# lab1_arhipov_usb_i2c.net
KiCad netlist of a schematic drawn in Altium Designer
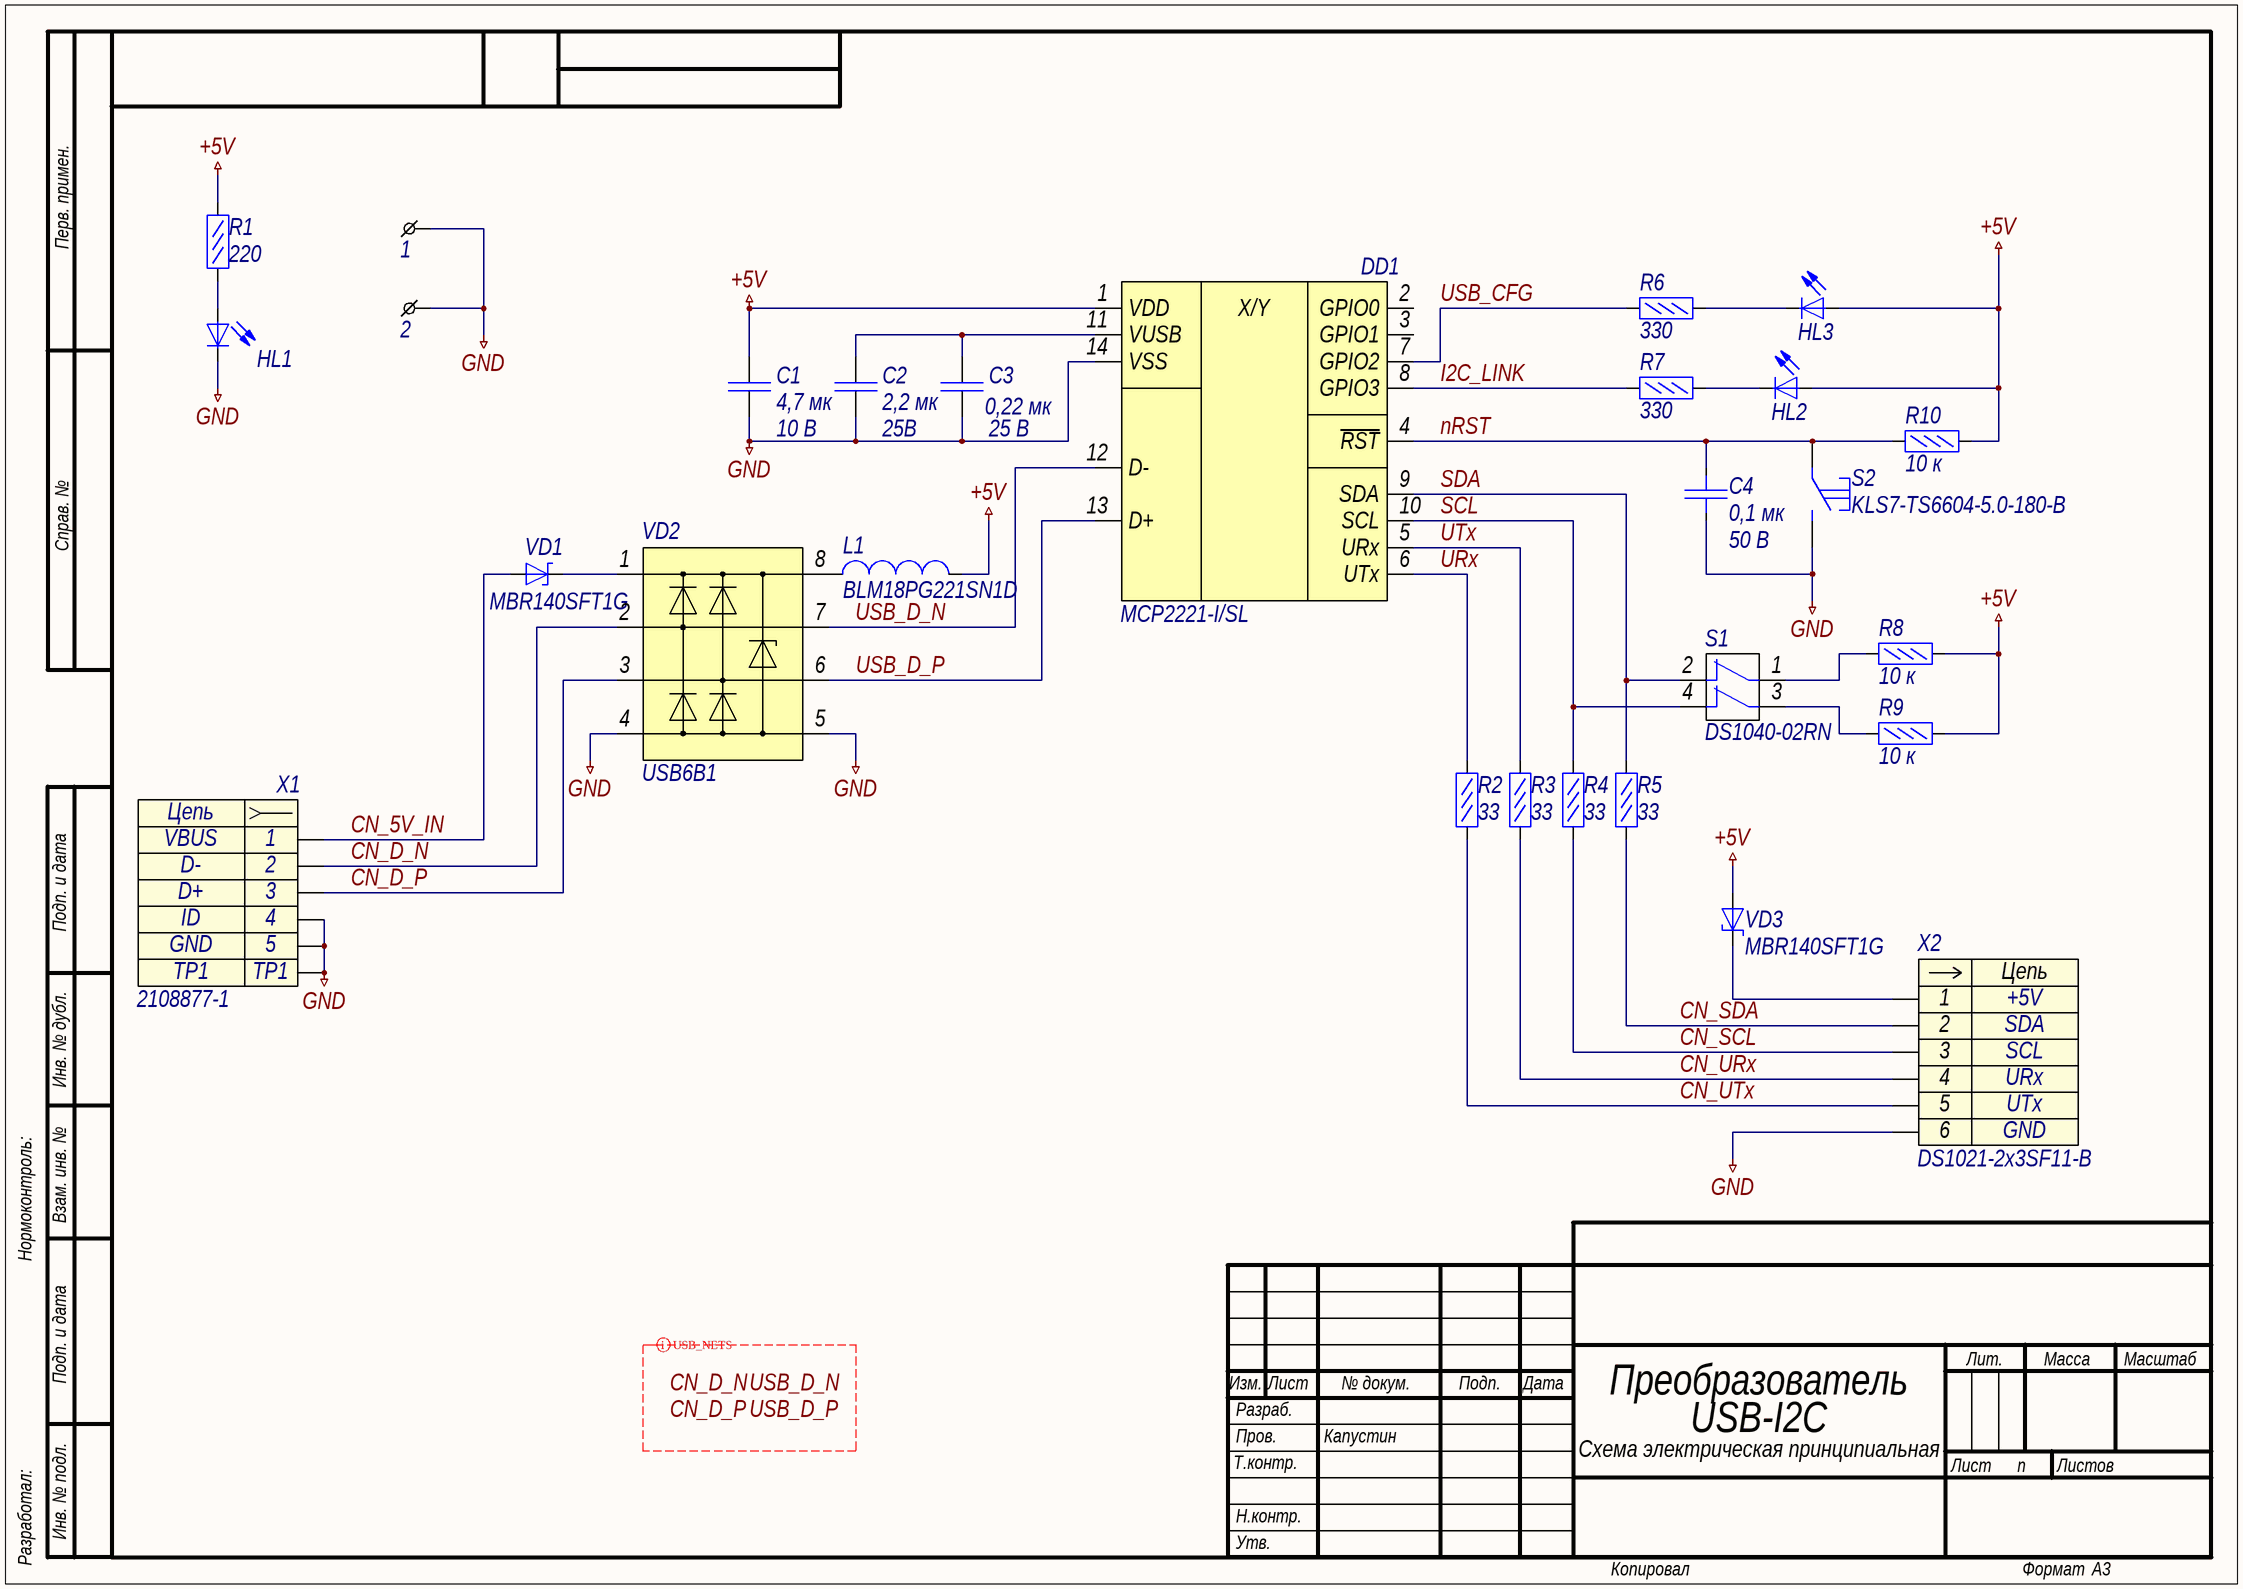
[diagram p0: lab1_arhipov_usb_i2c.SchDoc]

(export (version "E")
  (design (tool "Eeschema 10.0.6"))
  (components
    (comp (ref "1")
      (value "MOUNTING_HOLE")
      (footprint "HOLE_1,6X3,3")
      (libsource (lib "Lib") (part "Отверстие 1,6x3,3"))
    )
    (comp (ref "2")
      (value "MOUNTING_HOLE")
      (footprint "HOLE_1,6X3,3")
      (libsource (lib "Lib") (part "Отверстие 1,6x3,3"))
    )
    (comp (ref "C1")
      (value "4,7 мк")
      (footprint "c0805:C0805")
      (description "=Описание")
      (fields (field (name "НОМИНАЛЬНОЕ НАПРЯЖЕНИЕ") "10 В"))
      (libsource (lib "Database_Students") (part "C-10.0V4.7mkF"))
    )
    (comp (ref "C2")
      (value "2,2 мк")
      (footprint "c1206:C1206")
      (description "=Описание")
      (fields (field (name "НОМИНАЛЬНОЕ НАПРЯЖЕНИЕ") "25В"))
      (libsource (lib "Database_Students") (part "C-25.0V2.2mkF"))
    )
    (comp (ref "C3")
      (value "0,22 мк")
      (footprint "smd2220")
      (description "=Описание")
      (fields (field (name "НОМИНАЛЬНОЕ НАПРЯЖЕНИЕ") "25 В"))
      (libsource (lib "Database_Students") (part "C-25.0V0.22mkF"))
    )
    (comp (ref "C4")
      (value "0,1 мк")
      (footprint "C0603")
      (description "Конденсатор")
      (fields (field (name "НАПРЯЖЕНИЕ") "50 В"))
      (libsource (lib "Lib") (part "CL10B104KB8NNN"))
    )
    (comp (ref "DD1")
      (value "MCP2221-I/SL")
      (footprint "SOIC-14")
      (description "=Описание")
      (libsource (lib "Database_Students") (part "MCP2221-I/SL"))
    )
    (comp (ref "HL1") (value "KP-1608SGC") (footprint "D0603") (libsource (lib "Lib") (part "KP-1608SGC")))
    (comp (ref "HL2") (value "KP-1608SGC") (footprint "D0603") (libsource (lib "Lib") (part "KP-1608SGC")))
    (comp (ref "HL3") (value "KP-1608SGC") (footprint "D0603") (libsource (lib "Lib") (part "KP-1608SGC")))
    (comp (ref "L1")
      (value "BLM18PG221SN1D")
      (footprint "L0603")
      (libsource (lib "Lib") (part "BLM18PG221SN1D"))
    )
    (comp (ref "R1")
      (value "220")
      (footprint "R0603")
      (description "Резистор 0,063Вт")
      (libsource (lib "Lib") (part "RC0603FR-07220RL"))
    )
    (comp (ref "R2")
      (value "33")
      (footprint "R0603")
      (description "Резистор 0,063Вт")
      (libsource (lib "") (part "RC0603FR-0733RL_1"))
    )
    (comp (ref "R3")
      (value "33")
      (footprint "R0603")
      (description "Резистор 0,063Вт")
      (libsource (lib "Lib") (part "RC0603FR-0733RL"))
    )
    (comp (ref "R4")
      (value "33")
      (footprint "R0603")
      (description "Резистор 0,063Вт")
      (libsource (lib "Lib") (part "RC0603FR-0733RL"))
    )
    (comp (ref "R5")
      (value "33")
      (footprint "R0603")
      (description "Резистор 0,063Вт")
      (libsource (lib "Lib") (part "RC0603FR-0733RL"))
    )
    (comp (ref "R6")
      (value "330")
      (footprint "R0603")
      (description "Резистор 0,063Вт")
      (libsource (lib "Lib") (part "RC0603FR-07330RL"))
    )
    (comp (ref "R7")
      (value "330")
      (footprint "R0603")
      (description "Резистор 0,063Вт")
      (libsource (lib "Lib") (part "RC0603FR-07330RL"))
    )
    (comp (ref "R8")
      (value "10 к")
      (footprint "Lib:R0603")
      (description "Резистор 0,063Вт")
      (libsource (lib "Lib") (part "RC0603FR-0710KL"))
    )
    (comp (ref "R9")
      (value "10 к")
      (footprint "Lib:R0603")
      (description "Резистор 0,063Вт")
      (libsource (lib "Lib") (part "RC0603FR-0710KL"))
    )
    (comp (ref "R10")
      (value "10 к")
      (footprint "R0603")
      (description "Резистор 0,063Вт")
      (libsource (lib "Lib") (part "RC0603FR-0710KL"))
    )
    (comp (ref "S1")
      (value "DS1040-02RN")
      (footprint "DS1040-02RN")
      (description "=Описание")
      (libsource (lib "Database_Students") (part "SWITCH-4C"))
    )
    (comp (ref "S2")
      (value "KLS7-TS6604-5.0-180-B")
      (footprint "KLS7-TS6604-5.0-180-B")
      (description "=Описание")
      (libsource (lib "Database_Students") (part "BUTTON"))
    )
    (comp (ref "VD1")
      (value "MBR140SFT1G")
      (footprint "Lib:SOD-123FL_290X180X98")
      (libsource (lib "Lib") (part "MBR140SFT1G"))
    )
    (comp (ref "VD2") (value "USB6B1") (footprint "SO-8") (libsource (lib "Lib") (part "USB6B1")))
    (comp (ref "VD3")
      (value "MBR140SFT1G")
      (footprint "SOD-123FL_290X180X98")
      (libsource (lib "Lib") (part "MBR140SFT1G"))
    )
    (comp (ref "X1")
      (value "2108877-1")
      (footprint "2108877-1")
      (libsource (lib "2108877-1_micro_usb-b") (part "2108877-1_micro_usb-b"))
    )
    (comp (ref "X2")
      (value "DS1021-2x3SF11-B")
      (footprint "DS1021-2X3SF11-B")
      (description "=Описание")
      (libsource (lib "Database_Students") (part "HEADER-6-PLG"))
    )
  )
  (nets
    (net (code "1") (name "+5V") (class "Default")
      (node (ref "C1") (pin "1") (pinfunction "1_1") (pintype "passive"))
      (node (ref "DD1") (pin "1") (pinfunction "VDD_1") (pintype "passive"))
      (node (ref "HL2") (pin "1") (pinfunction "A_1") (pintype "passive"))
      (node (ref "HL3") (pin "1") (pinfunction "A_1") (pintype "passive"))
      (node (ref "L1") (pin "2") (pinfunction "2_2") (pintype "passive"))
      (node (ref "R1") (pin "2") (pinfunction "2_2") (pintype "passive"))
      (node (ref "R10") (pin "2") (pinfunction "2_2") (pintype "passive"))
      (node (ref "R8") (pin "2") (pinfunction "2_2") (pintype "passive"))
      (node (ref "R9") (pin "2") (pinfunction "2_2") (pintype "passive"))
      (node (ref "VD3") (pin "1") (pinfunction "A_1") (pintype "passive"))
    )
    (net (code "2") (name "/CN_5V_IN") (class "Default")
      (node (ref "VD1") (pin "1") (pinfunction "A_1") (pintype "passive"))
      (node (ref "X1") (pin "1") (pinfunction "1_1") (pintype "passive"))
    )
    (net (code "3") (name "/CN_D_N") (class "Default")
      (node (ref "VD2") (pin "2") (pintype "passive"))
      (node (ref "X1") (pin "2") (pinfunction "2_2") (pintype "passive"))
    )
    (net (code "4") (name "/CN_D_P") (class "Default")
      (node (ref "VD2") (pin "3") (pintype "passive"))
      (node (ref "X1") (pin "3") (pinfunction "3_3") (pintype "passive"))
    )
    (net (code "5") (name "/CN_SCL") (class "Default")
      (node (ref "R4") (pin "1") (pinfunction "1_1") (pintype "passive"))
      (node (ref "X2") (pin "3") (pinfunction "3_3") (pintype "passive"))
    )
    (net (code "6") (name "/CN_SDA") (class "Default")
      (node (ref "R5") (pin "1") (pinfunction "1_1") (pintype "passive"))
      (node (ref "X2") (pin "2") (pinfunction "2_2") (pintype "passive"))
    )
    (net (code "7") (name "/CN_URx") (class "Default")
      (node (ref "R3") (pin "1") (pinfunction "1_1") (pintype "passive"))
      (node (ref "X2") (pin "4") (pinfunction "4_4") (pintype "passive"))
    )
    (net (code "8") (name "/CN_UTx") (class "Default")
      (node (ref "R2") (pin "2") (pinfunction "2_2") (pintype "passive"))
      (node (ref "X2") (pin "5") (pinfunction "5_5") (pintype "passive"))
    )
    (net (code "9") (name "/I2C_LINK") (class "Default")
      (node (ref "DD1") (pin "8") (pinfunction "GPIO3_8") (pintype "passive"))
      (node (ref "R7") (pin "1") (pinfunction "1_1") (pintype "passive"))
    )
    (net (code "10") (name "/SCL") (class "Default")
      (node (ref "DD1") (pin "10") (pinfunction "SCL_10") (pintype "passive"))
      (node (ref "R4") (pin "2") (pinfunction "2_2") (pintype "passive"))
      (node (ref "S1") (pin "4") (pinfunction "4_4") (pintype "passive"))
    )
    (net (code "11") (name "/SDA") (class "Default")
      (node (ref "DD1") (pin "9") (pinfunction "SDA_9") (pintype "passive"))
      (node (ref "R5") (pin "2") (pinfunction "2_2") (pintype "passive"))
      (node (ref "S1") (pin "2") (pinfunction "2_2") (pintype "passive"))
    )
    (net (code "12") (name "/URx") (class "Default")
      (node (ref "DD1") (pin "6") (pinfunction "UTx_6") (pintype "passive"))
      (node (ref "R2") (pin "1") (pinfunction "1_1") (pintype "passive"))
    )
    (net (code "13") (name "/USB_CFG") (class "Default")
      (node (ref "DD1") (pin "7") (pinfunction "GPIO2_7") (pintype "passive"))
      (node (ref "R6") (pin "1") (pinfunction "1_1") (pintype "passive"))
    )
    (net (code "14") (name "/USB_D_N") (class "Default")
      (node (ref "DD1") (pin "12") (pinfunction "D-_12") (pintype "passive"))
      (node (ref "VD2") (pin "7") (pintype "passive"))
    )
    (net (code "15") (name "/USB_D_P") (class "Default")
      (node (ref "DD1") (pin "13") (pinfunction "D+_13") (pintype "passive"))
      (node (ref "VD2") (pin "6") (pintype "passive"))
    )
    (net (code "16") (name "/UTx") (class "Default")
      (node (ref "DD1") (pin "5") (pinfunction "URx_5") (pintype "passive"))
      (node (ref "R3") (pin "2") (pinfunction "2_2") (pintype "passive"))
    )
    (net (code "17") (name "/nRST") (class "Default")
      (node (ref "C4") (pin "2") (pinfunction "2_2") (pintype "passive"))
      (node (ref "DD1") (pin "4") (pinfunction "~{RST}_4") (pintype "passive"))
      (node (ref "R10") (pin "1") (pinfunction "1_1") (pintype "passive"))
      (node (ref "S2") (pin "1") (pinfunction "1_1") (pintype "passive"))
    )
    (net (code "18") (name "GND") (class "Default")
      (node (ref "1") (pin "1") (pinfunction "1_1") (pintype "passive"))
      (node (ref "2") (pin "1") (pinfunction "1_1") (pintype "passive"))
      (node (ref "C1") (pin "2") (pinfunction "2_2") (pintype "passive"))
      (node (ref "C2") (pin "1") (pinfunction "1_1") (pintype "passive"))
      (node (ref "C3") (pin "1") (pinfunction "1_1") (pintype "passive"))
      (node (ref "C4") (pin "1") (pinfunction "1_1") (pintype "passive"))
      (node (ref "DD1") (pin "14") (pinfunction "VSS_14") (pintype "passive"))
      (node (ref "HL1") (pin "2") (pinfunction "K_2") (pintype "passive"))
      (node (ref "S2") (pin "2") (pinfunction "2_2") (pintype "passive"))
      (node (ref "VD2") (pin "4") (pintype "passive"))
      (node (ref "VD2") (pin "5") (pintype "passive"))
      (node (ref "X1") (pin "4") (pinfunction "4_4") (pintype "passive"))
      (node (ref "X1") (pin "5") (pinfunction "5_5") (pintype "passive"))
      (node (ref "X1") (pin "TP1") (pinfunction "TP1_TP1") (pintype "passive"))
      (node (ref "X2") (pin "6") (pinfunction "6_6") (pintype "passive"))
    )
    (net (code "19") (name "Net-(DD1-VUSB)") (class "Default")
      (node (ref "C2") (pin "2") (pinfunction "2_2") (pintype "passive"))
      (node (ref "C3") (pin "2") (pinfunction "2_2") (pintype "passive"))
      (node (ref "DD1") (pin "11") (pinfunction "VUSB_11") (pintype "passive"))
    )
    (net (code "20") (name "Net-(HL1-A)") (class "Default")
      (node (ref "HL1") (pin "1") (pinfunction "A_1") (pintype "passive"))
      (node (ref "R1") (pin "1") (pinfunction "1_1") (pintype "passive"))
    )
    (net (code "21") (name "Net-(HL2-K)") (class "Default")
      (node (ref "HL2") (pin "2") (pinfunction "K_2") (pintype "passive"))
      (node (ref "R7") (pin "2") (pinfunction "2_2") (pintype "passive"))
    )
    (net (code "22") (name "Net-(HL3-K)") (class "Default")
      (node (ref "HL3") (pin "2") (pinfunction "K_2") (pintype "passive"))
      (node (ref "R6") (pin "2") (pinfunction "2_2") (pintype "passive"))
    )
    (net (code "23") (name "Net-(L1-Pad1)") (class "Default")
      (node (ref "L1") (pin "1") (pinfunction "1_1") (pintype "passive"))
      (node (ref "VD2") (pin "8") (pintype "passive"))
    )
    (net (code "24") (name "Net-(R8-Pad1)") (class "Default")
      (node (ref "R8") (pin "1") (pinfunction "1_1") (pintype "passive"))
      (node (ref "S1") (pin "1") (pinfunction "1_1") (pintype "passive"))
    )
    (net (code "25") (name "Net-(R9-Pad1)") (class "Default")
      (node (ref "R9") (pin "1") (pinfunction "1_1") (pintype "passive"))
      (node (ref "S1") (pin "3") (pinfunction "3_3") (pintype "passive"))
    )
    (net (code "26") (name "Net-(VD1-K)") (class "Default")
      (node (ref "VD1") (pin "2") (pinfunction "K_2") (pintype "passive"))
      (node (ref "VD2") (pin "1") (pintype "passive"))
    )
    (net (code "27") (name "Net-(VD3-K)") (class "Default")
      (node (ref "VD3") (pin "2") (pinfunction "K_2") (pintype "passive"))
      (node (ref "X2") (pin "1") (pinfunction "1_1") (pintype "passive"))
    )
    (net (code "28") (name "unconnected-(DD1-GPIO0-Pad2)") (class "Default")
      (node (ref "DD1") (pin "2") (pinfunction "GPIO0_2") (pintype "passive"))
    )
    (net (code "29") (name "unconnected-(DD1-GPIO1-Pad3)") (class "Default")
      (node (ref "DD1") (pin "3") (pinfunction "GPIO1_3") (pintype "passive"))
    )
  )
)
